# display_adapter.net
KiCad netlist of a schematic drawn in EAGLE
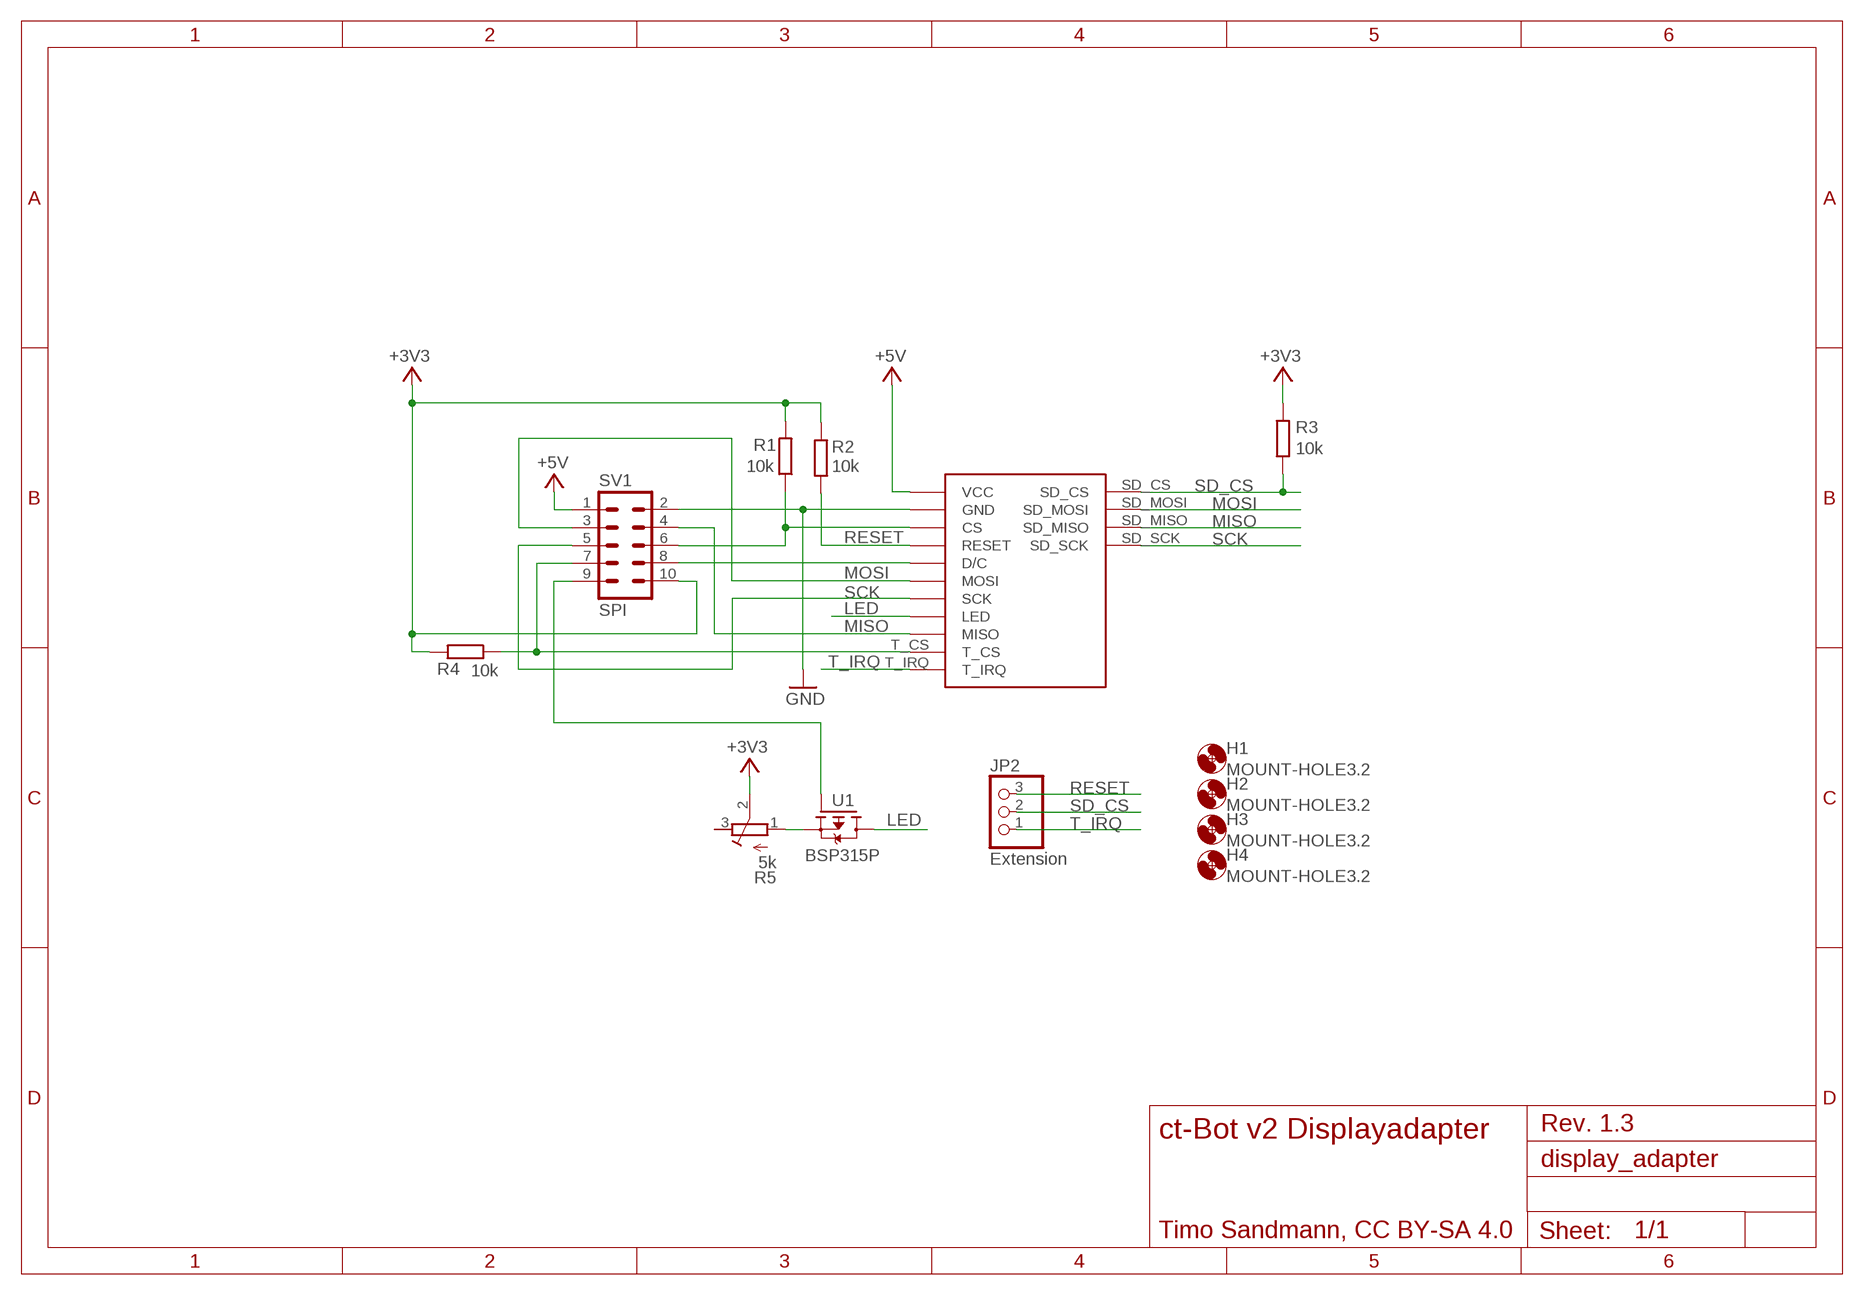
[diagram p0: schematic, sheet 1]

(export (version "E")
  (design (tool "Eeschema 10.0.6"))
  (components
    (comp (ref "H1")
      (value "MOUNT-HOLE3.2")
      (footprint "eagle-import:3,2")
      (libsource (lib "eagle-import") (part "MOUNT-HOLE3.2"))
    )
    (comp (ref "H2")
      (value "MOUNT-HOLE3.2")
      (footprint "eagle-import:3,2")
      (libsource (lib "eagle-import") (part "MOUNT-HOLE3.2"))
    )
    (comp (ref "H3")
      (value "MOUNT-HOLE3.2")
      (footprint "eagle-import:3,2")
      (libsource (lib "eagle-import") (part "MOUNT-HOLE3.2"))
    )
    (comp (ref "H4")
      (value "MOUNT-HOLE3.2")
      (footprint "eagle-import:3,2")
      (libsource (lib "eagle-import") (part "MOUNT-HOLE3.2"))
    )
    (comp (ref "J1")
      (value "SPI_TFT_DISPLAY_TOUCH")
      (footprint "eagle-import:SPI_DISPLAY_TOUCH")
      (libsource (lib "eagle-import") (part "SPI_TFT_DISPLAY_TOUCH"))
    )
    (comp (ref "JP2")
      (value "Extension")
      (footprint "eagle-import:1X03")
      (libsource (lib "eagle-import") (part "PINHD-1X3"))
    )
    (comp (ref "R1")
      (value "10k")
      (footprint "eagle-import:0204_7")
      (libsource (lib "eagle-import") (part "R-EU_0204/7"))
    )
    (comp (ref "R2")
      (value "10k")
      (footprint "eagle-import:0204_7")
      (libsource (lib "eagle-import") (part "R-EU_0204/7"))
    )
    (comp (ref "R3")
      (value "10k")
      (footprint "eagle-import:0204_7")
      (libsource (lib "eagle-import") (part "R-EU_0204/7"))
    )
    (comp (ref "R4")
      (value "10k")
      (footprint "eagle-import:0204_7")
      (libsource (lib "eagle-import") (part "R-EU_0204/7"))
    )
    (comp (ref "R5")
      (value "5k")
      (footprint "eagle-import:RTRIM64W")
      (libsource (lib "eagle-import") (part "R-TRIMM64W"))
    )
    (comp (ref "SV1")
      (value "SPI")
      (footprint "eagle-import:ML10")
      (fields (field (name "SPICEPREFIX") "X"))
      (libsource (lib "eagle-import") (part "ML10"))
    )
    (comp (ref "U1")
      (value "BSP315P")
      (footprint "eagle-import:PG-SOT-223")
      (libsource (lib "eagle-import") (part "BSP315P"))
    )
  )
  (nets
    (net (code "1") (name "+3V3") (class "Default")
      (node (ref "R1") (pin "2") (pinfunction "2_2") (pintype "passive"))
      (node (ref "R2") (pin "2") (pinfunction "2_2") (pintype "passive"))
      (node (ref "R3") (pin "2") (pinfunction "2_2") (pintype "passive"))
      (node (ref "R4") (pin "2") (pinfunction "2_2") (pintype "passive"))
      (node (ref "R5") (pin "2") (pinfunction "S_2") (pintype "passive"))
      (node (ref "SV1") (pin "10") (pinfunction "10_10") (pintype "passive"))
    )
    (net (code "2") (name "+5V") (class "Default")
      (node (ref "J1") (pin "VCC") (pinfunction "VCC_VCC") (pintype "power_in"))
      (node (ref "SV1") (pin "1") (pinfunction "1_1") (pintype "passive"))
    )
    (net (code "3") (name "/LED") (class "Default")
      (node (ref "J1") (pin "LED") (pinfunction "LED_LED") (pintype "bidirectional"))
      (node (ref "U1") (pin "2") (pinfunction "D_2") (pintype "passive"))
      (node (ref "U1") (pin "4") (pinfunction "D_4") (pintype "passive"))
    )
    (net (code "4") (name "/MISO") (class "Default")
      (node (ref "J1") (pin "MISO") (pinfunction "MISO_MISO") (pintype "bidirectional"))
      (node (ref "J1") (pin "SD_MISO") (pinfunction "SD_MISO_SD_MISO") (pintype "bidirectional"))
      (node (ref "J1") (pin "T_MISO") (pinfunction "MISO_T_MISO") (pintype "bidirectional"))
      (node (ref "SV1") (pin "4") (pinfunction "4_4") (pintype "passive"))
    )
    (net (code "5") (name "/MOSI") (class "Default")
      (node (ref "J1") (pin "MOSI") (pinfunction "MOSI_MOSI") (pintype "bidirectional"))
      (node (ref "J1") (pin "SD_MOSI") (pinfunction "SD_MOSI_SD_MOSI") (pintype "bidirectional"))
      (node (ref "J1") (pin "T_MOSI") (pinfunction "MOSI_T_MOSI") (pintype "bidirectional"))
      (node (ref "SV1") (pin "3") (pinfunction "3_3") (pintype "passive"))
    )
    (net (code "6") (name "/RESET") (class "Default")
      (node (ref "J1") (pin "RESET") (pinfunction "RESET_RESET") (pintype "bidirectional"))
      (node (ref "JP2") (pin "3") (pinfunction "3_3") (pintype "passive"))
      (node (ref "R2") (pin "1") (pinfunction "1_1") (pintype "passive"))
    )
    (net (code "7") (name "/SCK") (class "Default")
      (node (ref "J1") (pin "SCK") (pinfunction "SCK_SCK") (pintype "bidirectional"))
      (node (ref "J1") (pin "SD_SCK") (pinfunction "SD_SCK_SD_SCK") (pintype "bidirectional"))
      (node (ref "J1") (pin "T_SCK") (pinfunction "SCK_T_SCK") (pintype "bidirectional"))
      (node (ref "SV1") (pin "5") (pinfunction "5_5") (pintype "passive"))
    )
    (net (code "8") (name "/SD_CS") (class "Default")
      (node (ref "J1") (pin "SD_CS") (pinfunction "SD_CS_SD_CS") (pintype "bidirectional"))
      (node (ref "JP2") (pin "2") (pinfunction "2_2") (pintype "passive"))
      (node (ref "R3") (pin "1") (pinfunction "1_1") (pintype "passive"))
    )
    (net (code "9") (name "/T_IRQ") (class "Default")
      (node (ref "J1") (pin "T_IRQ") (pinfunction "T_IRQ_T_IRQ") (pintype "bidirectional"))
      (node (ref "JP2") (pin "1") (pinfunction "1_1") (pintype "passive"))
    )
    (net (code "10") (name "GND") (class "Default")
      (node (ref "J1") (pin "GND") (pinfunction "GND_GND") (pintype "power_in"))
      (node (ref "SV1") (pin "2") (pinfunction "2_2") (pintype "passive"))
    )
    (net (code "11") (name "Net-(J1-PadCS)") (class "Default")
      (node (ref "J1") (pin "CS") (pinfunction "CS_CS") (pintype "bidirectional"))
      (node (ref "R1") (pin "1") (pinfunction "1_1") (pintype "passive"))
      (node (ref "SV1") (pin "6") (pinfunction "6_6") (pintype "passive"))
    )
    (net (code "12") (name "Net-(J1-PadD{slash}C)") (class "Default")
      (node (ref "J1") (pin "D/C") (pinfunction "D/C_D/C") (pintype "bidirectional"))
      (node (ref "SV1") (pin "8") (pinfunction "8_8") (pintype "passive"))
    )
    (net (code "13") (name "Net-(J1-PadT_CS)") (class "Default")
      (node (ref "J1") (pin "T_CS") (pinfunction "T_CS_T_CS") (pintype "bidirectional"))
      (node (ref "R4") (pin "1") (pinfunction "1_1") (pintype "passive"))
      (node (ref "SV1") (pin "7") (pinfunction "7_7") (pintype "passive"))
    )
    (net (code "14") (name "Net-(R5-A)") (class "Default")
      (node (ref "R5") (pin "1") (pinfunction "A_1") (pintype "passive"))
      (node (ref "U1") (pin "3") (pinfunction "S_3") (pintype "passive"))
    )
    (net (code "15") (name "Net-(U1-G)") (class "Default")
      (node (ref "SV1") (pin "9") (pinfunction "9_9") (pintype "passive"))
      (node (ref "U1") (pin "1") (pinfunction "G_1") (pintype "passive"))
    )
    (net (code "16") (name "unconnected-(R5-E-Pad3)") (class "Default")
      (node (ref "R5") (pin "3") (pinfunction "E_3") (pintype "passive"))
    )
  )
)
